# MayRuaMach.net
KiCad netlist of a schematic drawn in Altium Designer
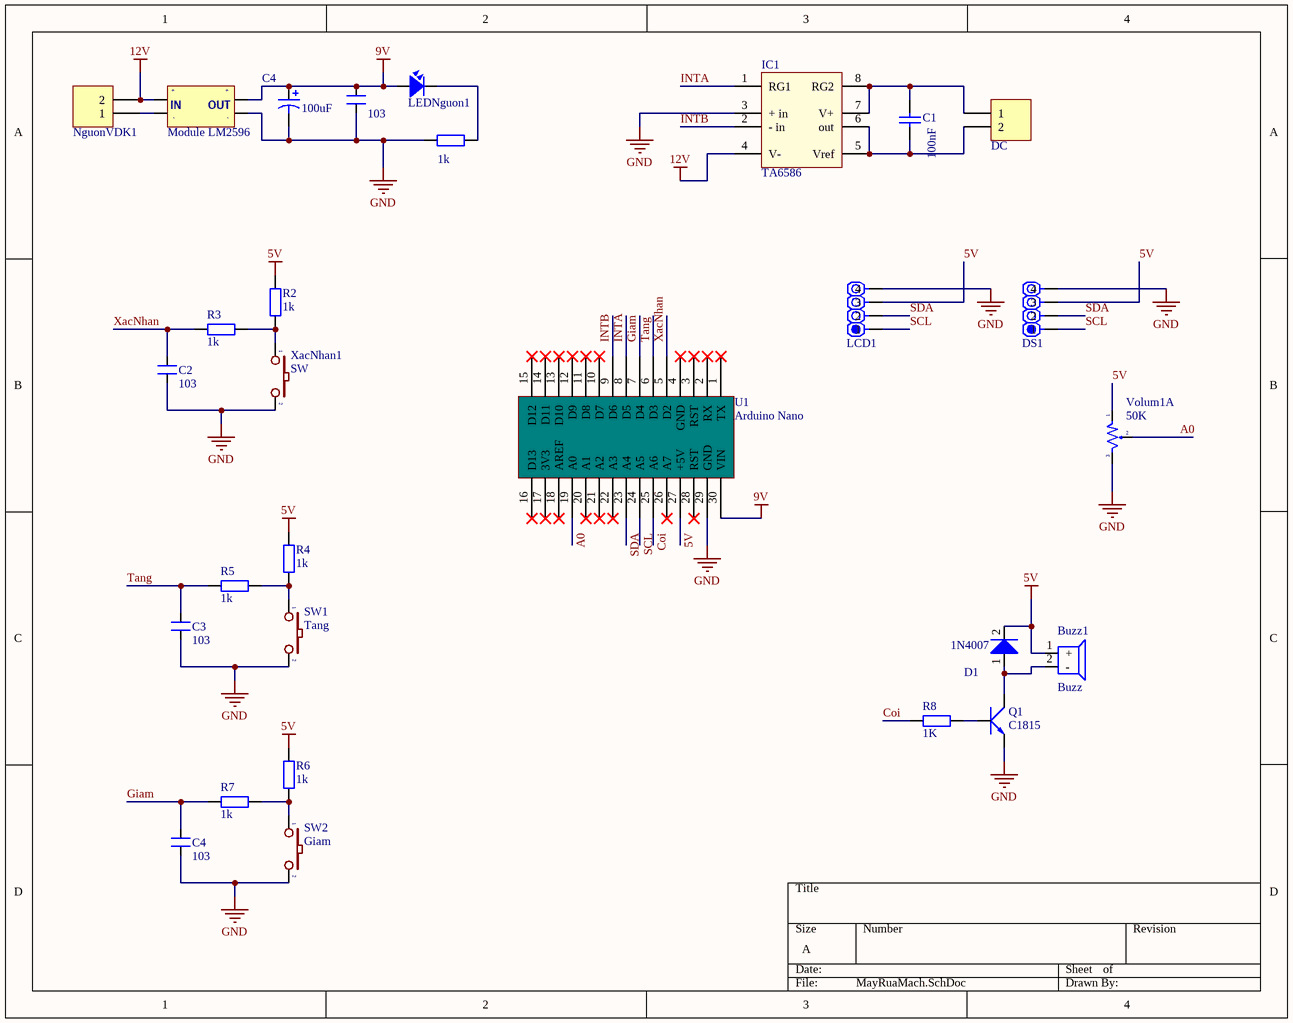
[diagram p0: MayRuaMach.SchDoc]

(export (version "E")
  (design (tool "Eeschema 10.0.6"))
  (components
    (comp (ref "Buzz1") (value "Buzz") (footprint "Buzz") (libsource (lib "VPMyLibrary") (part "Buzz")))
    (comp (ref "C1")
      (value "100nF")
      (footprint "CAPNTO2.54-3.05x1.78A")
      (description "CAP NPO CAPNTO 22pF 100V 10%")
      (fields (field (name "Comment") "5AK220KABAA"))
      (libsource (lib "NhomLib") (part "5AK220KABAA"))
    )
    (comp (ref "C2")
      (value "103")
      (footprint "CN1")
      (description "Cap np  1pF - 472pF")
      (libsource (lib "syhaunguyen") (part "CN1"))
    )
    (comp (ref "C3")
      (value "103")
      (footprint "CN1")
      (description "Cap np  1pF - 472pF")
      (libsource (lib "syhaunguyen") (part "CN1"))
    )
    (comp (ref "C4")
      (value "103")
      (footprint "CN1")
      (description "Cap np  1pF - 472pF")
      (libsource (lib "syhaunguyen") (part "CN1"))
    )
    (comp (ref "D1")
      (value "1N4007")
      (footprint "1N4007")
      (description "Diode LS 1A 1000V DO-41")
      (libsource (lib "LPSON") (part "1N4007"))
    )
    (comp (ref "DC")
      (value "Header 2_1")
      (footprint "HED2")
      (description "Header, 2-Pin")
      (fields (field (name "MANUFACTURER") "Generic Components"))
      (libsource (lib "") (part "Header 2_1_1"))
    )
    (comp (ref "DS1")
      (value "IO")
      (footprint "CON.HDR1X4L")
      (description "Header 1x4")
      (fields (field (name "PUBLISHER") "NKIM"))
      (libsource (lib "VPMyLibrary") (part "CON.HDR1x4"))
    )
    (comp (ref "IC1")
      (value "TA6586")
      (footprint "DIP8/W0.3")
      (description "Precision, Low Power  INSTRUMENTATION AMPLIFIER")
      (fields (field (name "DESIGNED BY") "VanDungEvn"))
      (libsource (lib "syhaunguyen") (part "INA118"))
    )
    (comp (ref "LCD1")
      (value "IO")
      (footprint "CON.HDR1X4L")
      (description "Header 1x4")
      (fields (field (name "PUBLISHER") "NKIM"))
      (libsource (lib "VPMyLibrary") (part "CON.HDR1x4"))
    )
    (comp (ref "LEDNguon1")
      (value "LED")
      (footprint "LED-5-RED")
      (description "LED Single colour Green and Red")
      (libsource (lib "syhaunguyen") (part "LED"))
    )
    (comp (ref "M1")
      (value "Module LM2596")
      (footprint "MODULE LM2596 MINI")
      (libsource (lib "LM2596") (part "Module LM2596 Mini"))
    )
    (comp (ref "NguonVDK1")
      (value "Header 2_1")
      (footprint "HED2")
      (description "Header, 2-Pin")
      (fields (field (name "MANUFACTURER") "Generic Components"))
      (libsource (lib "syhaunguyen") (part "Header 2_1"))
    )
    (comp (ref "Q1")
      (value "C1815")
      (footprint "QTO-92")
      (description "NPN 600mW, ECB")
      (libsource (lib "syhaunguyen") (part "C1815"))
    )
    (comp (ref "R1")
      (value "1k")
      (footprint "R1/4W")
      (description "Resistor 1/4W")
      (libsource (lib "syhaunguyen") (part "R1/4W"))
    )
    (comp (ref "R2")
      (value "1k")
      (footprint "R1/4W")
      (description "Resistor 1/4W")
      (libsource (lib "syhaunguyen") (part "R1/4W"))
    )
    (comp (ref "R3")
      (value "1k")
      (footprint "R1/4W")
      (description "Resistor 1/4W")
      (libsource (lib "syhaunguyen") (part "R1/4W"))
    )
    (comp (ref "R4")
      (value "1k")
      (footprint "R1/4W")
      (description "Resistor 1/4W")
      (libsource (lib "syhaunguyen") (part "R1/4W"))
    )
    (comp (ref "R5")
      (value "1k")
      (footprint "R1/4W")
      (description "Resistor 1/4W")
      (libsource (lib "syhaunguyen") (part "R1/4W"))
    )
    (comp (ref "R6")
      (value "1k")
      (footprint "R1/4W")
      (description "Resistor 1/4W")
      (libsource (lib "syhaunguyen") (part "R1/4W"))
    )
    (comp (ref "R7")
      (value "1k")
      (footprint "R1/4W")
      (description "Resistor 1/4W")
      (libsource (lib "syhaunguyen") (part "R1/4W"))
    )
    (comp (ref "R8")
      (value "1K")
      (footprint "R1/4W")
      (description "Resistor 1/4W")
      (libsource (lib "syhaunguyen") (part "R1/4W"))
    )
    (comp (ref "SW1")
      (value "Tang")
      (footprint "SW2")
      (description "Switch button 2 pin")
      (libsource (lib "syhaunguyen") (part "SW2"))
    )
    (comp (ref "SW2")
      (value "Giam")
      (footprint "SW2")
      (description "Switch button 2 pin")
      (libsource (lib "syhaunguyen") (part "SW2"))
    )
    (comp (ref "TuGom1")
      (value "103")
      (footprint "CN1")
      (description "Cap np  1pF - 472pF")
      (libsource (lib "syhaunguyen") (part "CN1"))
    )
    (comp (ref "TuHoa1")
      (value "100uF")
      (footprint "CP2/5")
      (description "Polarized Capacitor (Surface Mount)")
      (fields (field (name "ALTIUM_VALUE") "C4") (field (name "PUBLISHER") "Altium Limited"))
      (libsource (lib "syhaunguyen") (part "Cap Pol3"))
    )
    (comp (ref "U1")
      (value "Arduino Nano")
      (footprint "PCBComponent_1")
      (libsource (lib "Nano") (part "Component_1"))
    )
    (comp (ref "Volum1")
      (value "50K")
      (footprint "VOL-D")
      (description "Volume control Dual")
      (libsource (lib "syhaunguyen") (part "VOL-D"))
    )
    (comp (ref "XacNhan1")
      (value "SW")
      (footprint "SW2")
      (description "Switch button 2 pin")
      (libsource (lib "syhaunguyen") (part "SW2"))
    )
  )
  (nets
    (net (code "1") (name "/A0") (class "Default")
      (node (ref "U1") (pin "19") (pinfunction "A0_19") (pintype "passive"))
      (node (ref "Volum1") (pin "2") (pinfunction "2_2") (pintype "passive"))
    )
    (net (code "2") (name "/Coi") (class "Default")
      (node (ref "R8") (pin "1") (pinfunction "1_1") (pintype "passive"))
      (node (ref "U1") (pin "25") (pinfunction "A6_25") (pintype "passive"))
    )
    (net (code "3") (name "/Giam") (class "Default")
      (node (ref "C4") (pin "2") (pinfunction "2_2") (pintype "passive"))
      (node (ref "R7") (pin "1") (pinfunction "1_1") (pintype "passive"))
      (node (ref "U1") (pin "7") (pinfunction "D4_7") (pintype "passive"))
    )
    (net (code "4") (name "/INTA") (class "Default")
      (node (ref "IC1") (pin "1") (pinfunction "RG1_1") (pintype "passive"))
      (node (ref "U1") (pin "8") (pinfunction "D5_8") (pintype "passive"))
    )
    (net (code "5") (name "/INTB") (class "Default")
      (node (ref "IC1") (pin "2") (pinfunction "-_in_2") (pintype "passive"))
      (node (ref "U1") (pin "9") (pinfunction "D6_9") (pintype "passive"))
    )
    (net (code "6") (name "/SCL") (class "Default")
      (node (ref "DS1") (pin "1") (pinfunction "1_1") (pintype "passive"))
      (node (ref "LCD1") (pin "1") (pinfunction "1_1") (pintype "passive"))
      (node (ref "U1") (pin "24") (pinfunction "A5_24") (pintype "passive"))
    )
    (net (code "7") (name "/SDA") (class "Default")
      (node (ref "DS1") (pin "2") (pinfunction "2_2") (pintype "passive"))
      (node (ref "LCD1") (pin "2") (pinfunction "2_2") (pintype "passive"))
      (node (ref "U1") (pin "23") (pinfunction "A4_23") (pintype "passive"))
    )
    (net (code "8") (name "/Tang") (class "Default")
      (node (ref "C3") (pin "2") (pinfunction "2_2") (pintype "passive"))
      (node (ref "R5") (pin "1") (pinfunction "1_1") (pintype "passive"))
      (node (ref "U1") (pin "6") (pinfunction "D3_6") (pintype "passive"))
    )
    (net (code "9") (name "/XacNhan") (class "Default")
      (node (ref "C2") (pin "2") (pinfunction "2_2") (pintype "passive"))
      (node (ref "R3") (pin "1") (pinfunction "1_1") (pintype "passive"))
      (node (ref "U1") (pin "5") (pinfunction "D2_5") (pintype "passive"))
    )
    (net (code "10") (name "5V") (class "Default")
      (node (ref "Buzz1") (pin "1") (pinfunction "+_1") (pintype "passive"))
      (node (ref "D1") (pin "2") (pinfunction "K_2") (pintype "passive"))
      (node (ref "DS1") (pin "3") (pinfunction "3_3") (pintype "passive"))
      (node (ref "LCD1") (pin "3") (pinfunction "3_3") (pintype "passive"))
      (node (ref "R2") (pin "2") (pinfunction "2_2") (pintype "passive"))
      (node (ref "R4") (pin "2") (pinfunction "2_2") (pintype "passive"))
      (node (ref "R6") (pin "2") (pinfunction "2_2") (pintype "passive"))
      (node (ref "U1") (pin "27") (pinfunction "+5V_27") (pintype "passive"))
      (node (ref "Volum1") (pin "1") (pinfunction "1_1") (pintype "passive"))
    )
    (net (code "11") (name "9V") (class "Default")
      (node (ref "LEDNguon1") (pin "1") (pinfunction "1_1") (pintype "passive"))
      (node (ref "M1") (pin "3") (pinfunction "3_3") (pintype "passive"))
      (node (ref "TuGom1") (pin "2") (pinfunction "2_2") (pintype "passive"))
      (node (ref "TuHoa1") (pin "1") (pinfunction "1_1") (pintype "passive"))
      (node (ref "U1") (pin "30") (pinfunction "VIN_30") (pintype "passive"))
    )
    (net (code "12") (name "12V") (class "Default")
      (node (ref "IC1") (pin "4") (pinfunction "V-_4") (pintype "passive"))
      (node (ref "M1") (pin "1") (pinfunction "1_1") (pintype "passive"))
      (node (ref "NguonVDK1") (pin "2") (pinfunction "2_2") (pintype "passive"))
    )
    (net (code "13") (name "GND") (class "Default")
      (node (ref "C2") (pin "1") (pinfunction "1_1") (pintype "passive"))
      (node (ref "C3") (pin "1") (pinfunction "1_1") (pintype "passive"))
      (node (ref "C4") (pin "1") (pinfunction "1_1") (pintype "passive"))
      (node (ref "DS1") (pin "4") (pinfunction "4_4") (pintype "passive"))
      (node (ref "IC1") (pin "3") (pinfunction "+_in_3") (pintype "passive"))
      (node (ref "LCD1") (pin "4") (pinfunction "4_4") (pintype "passive"))
      (node (ref "M1") (pin "4") (pinfunction "4_4") (pintype "passive"))
      (node (ref "Q1") (pin "1") (pinfunction "E_1") (pintype "passive"))
      (node (ref "R1") (pin "1") (pinfunction "1_1") (pintype "passive"))
      (node (ref "SW1") (pin "2") (pinfunction "2_2") (pintype "passive"))
      (node (ref "SW2") (pin "2") (pinfunction "2_2") (pintype "passive"))
      (node (ref "TuGom1") (pin "1") (pinfunction "1_1") (pintype "passive"))
      (node (ref "TuHoa1") (pin "2") (pinfunction "2_2") (pintype "passive"))
      (node (ref "U1") (pin "29") (pinfunction "GND_29") (pintype "passive"))
      (node (ref "Volum1") (pin "3") (pinfunction "3_3") (pintype "passive"))
      (node (ref "XacNhan1") (pin "2") (pinfunction "2_2") (pintype "passive"))
    )
    (net (code "14") (name "Net-(Buzz1--)") (class "Default")
      (node (ref "Buzz1") (pin "2") (pinfunction "-_2") (pintype "passive"))
      (node (ref "D1") (pin "1") (pinfunction "A_1") (pintype "passive"))
      (node (ref "Q1") (pin "2") (pinfunction "C_2") (pintype "passive"))
    )
    (net (code "15") (name "Net-(IC1-RG2)") (class "Default")
      (node (ref "C1") (pin "1") (pinfunction "1_1") (pintype "passive"))
      (node (ref "DC") (pin "1") (pinfunction "1_1") (pintype "passive"))
      (node (ref "IC1") (pin "7") (pinfunction "V+_7") (pintype "passive"))
      (node (ref "IC1") (pin "8") (pinfunction "RG2_8") (pintype "passive"))
    )
    (net (code "16") (name "Net-(IC1-Vref)") (class "Default")
      (node (ref "C1") (pin "2") (pinfunction "2_2") (pintype "passive"))
      (node (ref "DC") (pin "2") (pinfunction "2_2") (pintype "passive"))
      (node (ref "IC1") (pin "5") (pinfunction "Vref_5") (pintype "passive"))
      (node (ref "IC1") (pin "6") (pinfunction "out_6") (pintype "passive"))
    )
    (net (code "17") (name "Net-(LEDNguon1-Pad2)") (class "Default")
      (node (ref "LEDNguon1") (pin "2") (pinfunction "2_2") (pintype "passive"))
      (node (ref "R1") (pin "2") (pinfunction "2_2") (pintype "passive"))
    )
    (net (code "18") (name "Net-(M1-Pad2)") (class "Default")
      (node (ref "M1") (pin "2") (pinfunction "2_2") (pintype "passive"))
      (node (ref "NguonVDK1") (pin "1") (pinfunction "1_1") (pintype "passive"))
    )
    (net (code "19") (name "Net-(Q1-B)") (class "Default")
      (node (ref "Q1") (pin "3") (pinfunction "B_3") (pintype "passive"))
      (node (ref "R8") (pin "2") (pinfunction "2_2") (pintype "passive"))
    )
    (net (code "20") (name "Net-(R2-Pad1)") (class "Default")
      (node (ref "R2") (pin "1") (pinfunction "1_1") (pintype "passive"))
      (node (ref "R3") (pin "2") (pinfunction "2_2") (pintype "passive"))
      (node (ref "XacNhan1") (pin "1") (pinfunction "1_1") (pintype "passive"))
    )
    (net (code "21") (name "Net-(R4-Pad1)") (class "Default")
      (node (ref "R4") (pin "1") (pinfunction "1_1") (pintype "passive"))
      (node (ref "R5") (pin "2") (pinfunction "2_2") (pintype "passive"))
      (node (ref "SW1") (pin "1") (pinfunction "1_1") (pintype "passive"))
    )
    (net (code "22") (name "Net-(R6-Pad1)") (class "Default")
      (node (ref "R6") (pin "1") (pinfunction "1_1") (pintype "passive"))
      (node (ref "R7") (pin "2") (pinfunction "2_2") (pintype "passive"))
      (node (ref "SW2") (pin "1") (pinfunction "1_1") (pintype "passive"))
    )
    (net (code "23") (name "unconnected-(U1-3V3-Pad17)") (class "Default")
      (node (ref "U1") (pin "17") (pinfunction "3V3_17") (pintype "passive+no_connect"))
    )
    (net (code "24") (name "unconnected-(U1-A1-Pad20)") (class "Default")
      (node (ref "U1") (pin "20") (pinfunction "A1_20") (pintype "passive+no_connect"))
    )
    (net (code "25") (name "unconnected-(U1-A2-Pad21)") (class "Default")
      (node (ref "U1") (pin "21") (pinfunction "A2_21") (pintype "passive+no_connect"))
    )
    (net (code "26") (name "unconnected-(U1-A3-Pad22)") (class "Default")
      (node (ref "U1") (pin "22") (pinfunction "A3_22") (pintype "passive+no_connect"))
    )
    (net (code "27") (name "unconnected-(U1-A7-Pad26)") (class "Default")
      (node (ref "U1") (pin "26") (pinfunction "A7_26") (pintype "passive+no_connect"))
    )
    (net (code "28") (name "unconnected-(U1-AREF-Pad18)") (class "Default")
      (node (ref "U1") (pin "18") (pinfunction "AREF_18") (pintype "passive+no_connect"))
    )
    (net (code "29") (name "unconnected-(U1-D7-Pad10)") (class "Default")
      (node (ref "U1") (pin "10") (pinfunction "D7_10") (pintype "passive+no_connect"))
    )
    (net (code "30") (name "unconnected-(U1-D8-Pad11)") (class "Default")
      (node (ref "U1") (pin "11") (pinfunction "D8_11") (pintype "passive+no_connect"))
    )
    (net (code "31") (name "unconnected-(U1-D9-Pad12)") (class "Default")
      (node (ref "U1") (pin "12") (pinfunction "D9_12") (pintype "passive+no_connect"))
    )
    (net (code "32") (name "unconnected-(U1-D10-Pad13)") (class "Default")
      (node (ref "U1") (pin "13") (pinfunction "D10_13") (pintype "passive+no_connect"))
    )
    (net (code "33") (name "unconnected-(U1-D11-Pad14)") (class "Default")
      (node (ref "U1") (pin "14") (pinfunction "D11_14") (pintype "passive+no_connect"))
    )
    (net (code "34") (name "unconnected-(U1-D12-Pad15)") (class "Default")
      (node (ref "U1") (pin "15") (pinfunction "D12_15") (pintype "passive+no_connect"))
    )
    (net (code "35") (name "unconnected-(U1-D13-Pad16)") (class "Default")
      (node (ref "U1") (pin "16") (pinfunction "D13_16") (pintype "passive+no_connect"))
    )
    (net (code "36") (name "unconnected-(U1-GND-Pad4)") (class "Default")
      (node (ref "U1") (pin "4") (pinfunction "GND_4") (pintype "passive+no_connect"))
    )
    (net (code "37") (name "unconnected-(U1-RST-Pad3)") (class "Default")
      (node (ref "U1") (pin "3") (pinfunction "RST_3") (pintype "passive+no_connect"))
    )
    (net (code "38") (name "unconnected-(U1-RST-Pad28)") (class "Default")
      (node (ref "U1") (pin "28") (pinfunction "RST_28") (pintype "passive+no_connect"))
    )
    (net (code "39") (name "unconnected-(U1-RX-Pad2)") (class "Default")
      (node (ref "U1") (pin "2") (pinfunction "RX_2") (pintype "passive+no_connect"))
    )
    (net (code "40") (name "unconnected-(U1-TX-Pad1)") (class "Default")
      (node (ref "U1") (pin "1") (pinfunction "TX_1") (pintype "passive+no_connect"))
    )
  )
)
